# FORKGUARD_MAIN_BOARD.net
KiCad netlist of a schematic drawn in EasyEDA Pro
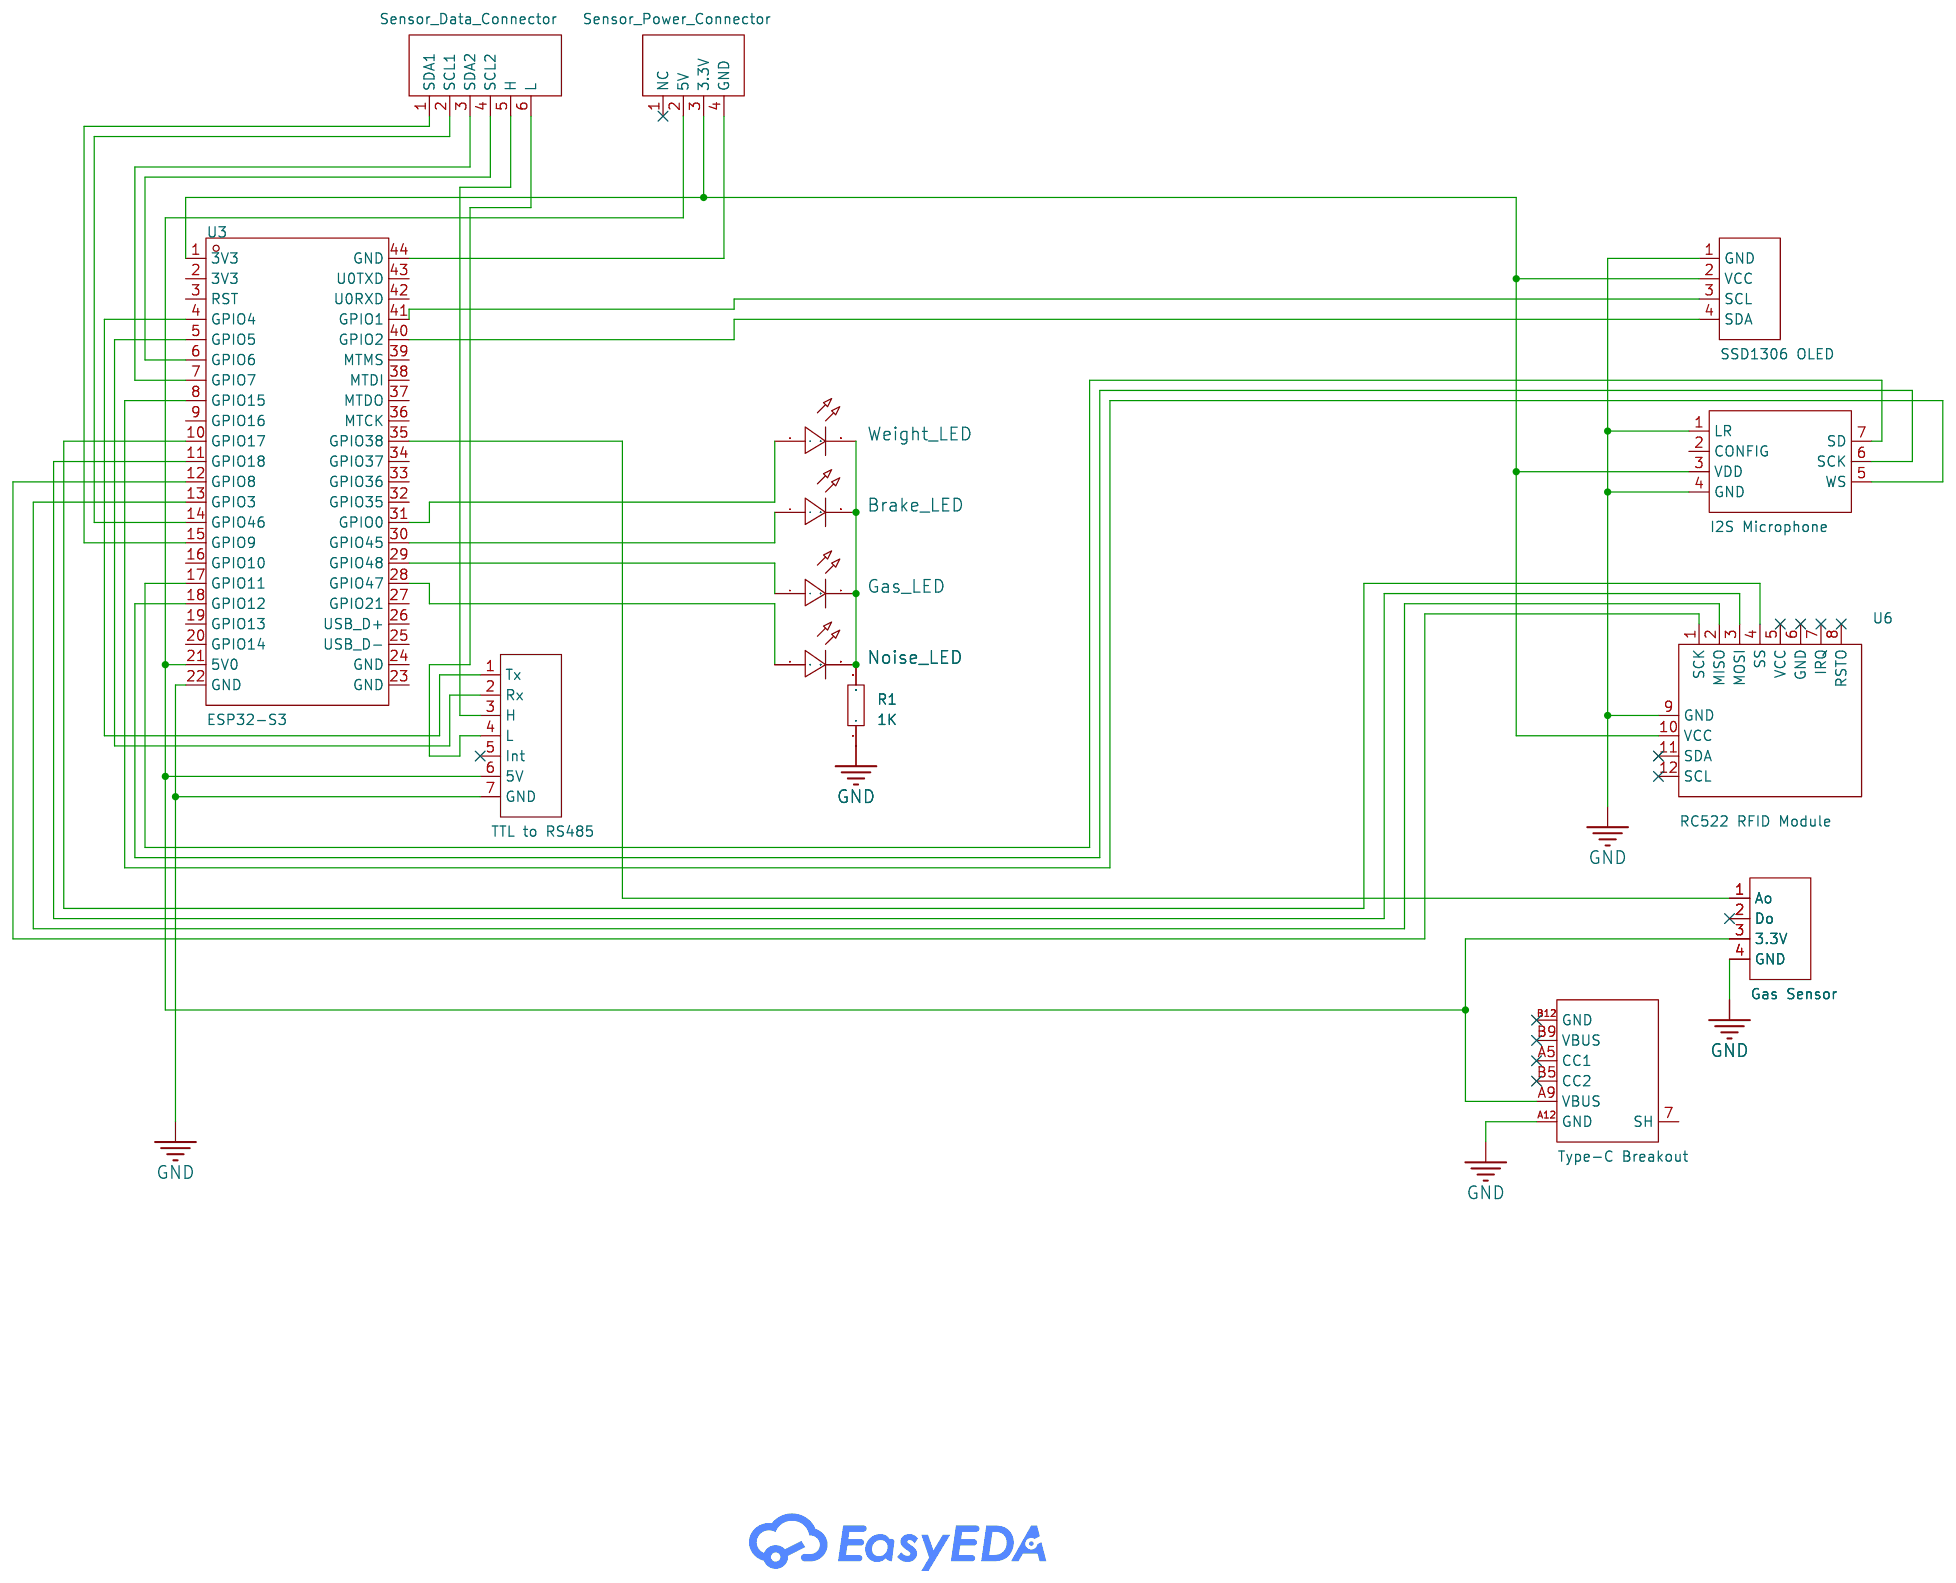
[diagram p0: schematic sheet]

(export (version "E")
  (design (tool "Eeschema 10.0.6"))
  (components
    (comp (ref "Brake_LED")
      (value "~")
      (footprint "easyedapro:LED0402-RD_YELLOW")
      (libsource (lib "easyedapro") (part "LED_R"))
    )
    (comp (ref "Display")
      (value "SSD1306 OLED")
      (footprint "easyedapro:OLED-TH_4P-L27.8-W27.3_MC096GW")
      (fields (field (name "Manufacturer Part") "MC096GW"))
      (libsource (lib "easyedapro") (part "MC096GW"))
    )
    (comp (ref "Gas_LED")
      (value "~")
      (footprint "easyedapro:LED0402-RD_YELLOW")
      (libsource (lib "easyedapro") (part "LED_R"))
    )
    (comp (ref "H1")
      (value "Sensor_Data_Connector")
      (footprint "easyedapro:HDR-TH_TW-06-01-T-S-150-085")
      (fields
        (field (name "Manufacturer Part") "TW-06-08-L-S-580-150")
        (field (name "Manufacturer") "SAMTEC")
      )
      (libsource (lib "easyedapro") (part "TW-06-08-L-S-580-150"))
    )
    (comp (ref "H2")
      (value "Sensor_Power_Connector")
      (footprint "easyedapro:HDR-TH_TW-04-06-T-S-433-120")
      (fields
        (field (name "Manufacturer Part") "TW-04-05-L-S-275-158")
        (field (name "Manufacturer") "SAMTEC")
      )
      (libsource (lib "easyedapro") (part "TW-04-05-L-S-275-158"))
    )
    (comp (ref "H5")
      (value "TTL to RS485")
      (footprint "easyedapro:HDR-TH_7P-P2.54_PBC07SAEN")
      (fields (field (name "Manufacturer Part") "PEC07SADN") (field (name "Manufacturer") "Sullins"))
      (libsource (lib "easyedapro") (part "PEC07SADN"))
    )
    (comp (ref "H6")
      (value "Gas Sensor")
      (footprint "easyedapro:HDR-TH_4P-P2.54-V-M_2")
      (fields (field (name "Manufacturer Part") "PEC04SFDN") (field (name "Manufacturer") "Sullins"))
      (libsource (lib "easyedapro") (part "PEC04SFDN"))
    )
    (comp (ref "Noise_LED")
      (value "~")
      (footprint "easyedapro:LED0402-RD_YELLOW")
      (libsource (lib "easyedapro") (part "LED_R"))
    )
    (comp (ref "R1") (value "10K") (footprint "easyedapro:R0603") (libsource (lib "easyedapro") (part "Res")))
    (comp (ref "U3")
      (value "ESP32-S3")
      (footprint "easyedapro:COMM-TH_L63.3-W25.4-P2.54-LS22.86")
      (fields (field (name "Manufacturer Part") "ESP32-S3-DEV-KIT-N8R8"))
      (libsource (lib "easyedapro") (part "ESP32-S3-DEV-KIT-N8R8"))
    )
    (comp (ref "U5")
      (value "I2S Microphone")
      (footprint "easyedapro:MIC-SMD_7P-L4.0-W3.0-P2.15-TL")
      (fields (field (name "Manufacturer Part") "DMM-4026-B-I2S-R") (field (name "Manufacturer") "PUIAUDIO"))
      (libsource (lib "easyedapro") (part "DMM-4026-B-I2S-R_C3171792"))
    )
    (comp (ref "U6")
      (value "RC522 RFID Module")
      (footprint "easyedapro:COMM-TH_L42.7-W40.4_PN532_NFC_RFID")
      (fields (field (name "Manufacturer Part") "PN532 NFC RFID Module v4"))
      (libsource (lib "easyedapro") (part "PN532 NFC RFID MODULE V4"))
    )
    (comp (ref "USB1")
      (value "Type-C Breakout")
      (footprint "easyedapro:USB-SMD_TYPE-C6P-ST")
      (fields (field (name "Manufacturer Part") "TCR51-65120601"))
      (libsource (lib "easyedapro") (part "TCR51-65120601"))
    )
    (comp (ref "Weight_LED")
      (value "~")
      (footprint "easyedapro:LED0402-RD_YELLOW")
      (libsource (lib "easyedapro") (part "LED_R"))
    )
  )
  (nets
    (net (code "1") (name "GND") (class "Default")
      (node (ref "Display") (pin "1") (pinfunction "GND_1") (pintype "unspecified"))
      (node (ref "H5") (pin "7") (pinfunction "GND_7") (pintype "unspecified"))
      (node (ref "H6") (pin "4") (pinfunction "GND_4") (pintype "unspecified"))
      (node (ref "R1") (pin "1") (pinfunction "1_1") (pintype "input"))
      (node (ref "U3") (pin "22") (pinfunction "GND_22") (pintype "unspecified"))
      (node (ref "U5") (pin "1") (pinfunction "LR_1") (pintype "unspecified"))
      (node (ref "U5") (pin "4") (pinfunction "GND_4") (pintype "unspecified"))
      (node (ref "U6") (pin "9") (pinfunction "GND_9") (pintype "unspecified"))
      (node (ref "USB1") (pin "A12") (pinfunction "GND_A12") (pintype "unspecified"))
    )
    (net (code "2") (name "Net-(Brake_LED-A)") (class "Default")
      (node (ref "Brake_LED") (pin "1") (pinfunction "A_1") (pintype "input"))
      (node (ref "U3") (pin "30") (pinfunction "GPIO45_30") (pintype "unspecified"))
    )
    (net (code "3") (name "Net-(Brake_LED-C)") (class "Default")
      (node (ref "Brake_LED") (pin "2") (pinfunction "C_2") (pintype "input"))
      (node (ref "Gas_LED") (pin "2") (pinfunction "C_2") (pintype "input"))
      (node (ref "Noise_LED") (pin "2") (pinfunction "C_2") (pintype "input"))
      (node (ref "R1") (pin "2") (pinfunction "2_2") (pintype "input"))
      (node (ref "Weight_LED") (pin "2") (pinfunction "C_2") (pintype "input"))
    )
    (net (code "4") (name "Net-(Display-SCL)") (class "Default")
      (node (ref "Display") (pin "3") (pinfunction "SCL_3") (pintype "unspecified"))
      (node (ref "U3") (pin "41") (pinfunction "GPIO1_41") (pintype "unspecified"))
    )
    (net (code "5") (name "Net-(Display-SDA)") (class "Default")
      (node (ref "Display") (pin "4") (pinfunction "SDA_4") (pintype "unspecified"))
      (node (ref "U3") (pin "40") (pinfunction "GPIO2_40") (pintype "unspecified"))
    )
    (net (code "6") (name "Net-(Display-VCC)") (class "Default")
      (node (ref "Display") (pin "2") (pinfunction "VCC_2") (pintype "unspecified"))
      (node (ref "H2") (pin "3") (pinfunction "3.3V_3") (pintype "unspecified"))
      (node (ref "U3") (pin "1") (pinfunction "3V3_1") (pintype "unspecified"))
      (node (ref "U5") (pin "3") (pinfunction "VDD_3") (pintype "unspecified"))
      (node (ref "U6") (pin "10") (pinfunction "VCC_10") (pintype "unspecified"))
    )
    (net (code "7") (name "Net-(Gas_LED-A)") (class "Default")
      (node (ref "Gas_LED") (pin "1") (pinfunction "A_1") (pintype "input"))
      (node (ref "U3") (pin "29") (pinfunction "GPIO48_29") (pintype "unspecified"))
    )
    (net (code "8") (name "Net-(H1-H)") (class "Default")
      (node (ref "H1") (pin "5") (pinfunction "H_5") (pintype "unspecified"))
      (node (ref "H5") (pin "3") (pinfunction "H_3") (pintype "unspecified"))
    )
    (net (code "9") (name "Net-(H1-L)") (class "Default")
      (node (ref "H1") (pin "6") (pinfunction "L_6") (pintype "unspecified"))
      (node (ref "H5") (pin "4") (pinfunction "L_4") (pintype "unspecified"))
    )
    (net (code "10") (name "Net-(H1-SCL1)") (class "Default")
      (node (ref "H1") (pin "2") (pinfunction "SCL1_2") (pintype "unspecified"))
      (node (ref "U3") (pin "14") (pinfunction "GPIO46_14") (pintype "unspecified"))
    )
    (net (code "11") (name "Net-(H1-SCL2)") (class "Default")
      (node (ref "H1") (pin "4") (pinfunction "SCL2_4") (pintype "unspecified"))
      (node (ref "U3") (pin "6") (pinfunction "GPIO6_6") (pintype "unspecified"))
    )
    (net (code "12") (name "Net-(H1-SDA1)") (class "Default")
      (node (ref "H1") (pin "1") (pinfunction "SDA1_1") (pintype "unspecified"))
      (node (ref "U3") (pin "15") (pinfunction "GPIO9_15") (pintype "unspecified"))
    )
    (net (code "13") (name "Net-(H1-SDA2)") (class "Default")
      (node (ref "H1") (pin "3") (pinfunction "SDA2_3") (pintype "unspecified"))
      (node (ref "U3") (pin "7") (pinfunction "GPIO7_7") (pintype "unspecified"))
    )
    (net (code "14") (name "Net-(H2-5V)") (class "Default")
      (node (ref "H2") (pin "2") (pinfunction "5V_2") (pintype "unspecified"))
      (node (ref "H5") (pin "6") (pinfunction "5V_6") (pintype "unspecified"))
      (node (ref "H6") (pin "3") (pinfunction "3.3V_3") (pintype "unspecified"))
      (node (ref "U3") (pin "21") (pinfunction "5V0_21") (pintype "unspecified"))
      (node (ref "USB1") (pin "A9") (pinfunction "VBUS_A9") (pintype "unspecified"))
    )
    (net (code "15") (name "Net-(H2-GND)") (class "Default")
      (node (ref "H2") (pin "4") (pinfunction "GND_4") (pintype "unspecified"))
      (node (ref "U3") (pin "44") (pinfunction "GND_44") (pintype "unspecified"))
    )
    (net (code "16") (name "Net-(H5-Rx)") (class "Default")
      (node (ref "H5") (pin "2") (pinfunction "Rx_2") (pintype "unspecified"))
      (node (ref "U3") (pin "5") (pinfunction "GPIO5_5") (pintype "unspecified"))
    )
    (net (code "17") (name "Net-(H5-Tx)") (class "Default")
      (node (ref "H5") (pin "1") (pinfunction "Tx_1") (pintype "unspecified"))
      (node (ref "U3") (pin "4") (pinfunction "GPIO4_4") (pintype "unspecified"))
    )
    (net (code "18") (name "Net-(H6-Ao)") (class "Default")
      (node (ref "H6") (pin "1") (pinfunction "Ao_1") (pintype "unspecified"))
      (node (ref "U3") (pin "35") (pinfunction "GPIO38_35") (pintype "unspecified"))
    )
    (net (code "19") (name "Net-(Noise_LED-A)") (class "Default")
      (node (ref "Noise_LED") (pin "1") (pinfunction "A_1") (pintype "input"))
      (node (ref "U3") (pin "28") (pinfunction "GPIO47_28") (pintype "unspecified"))
    )
    (net (code "20") (name "Net-(U3-GPIO0)") (class "Default")
      (node (ref "U3") (pin "31") (pinfunction "GPIO0_31") (pintype "unspecified"))
      (node (ref "Weight_LED") (pin "1") (pinfunction "A_1") (pintype "input"))
    )
    (net (code "21") (name "Net-(U3-GPIO3)") (class "Default")
      (node (ref "U3") (pin "13") (pinfunction "GPIO3_13") (pintype "unspecified"))
      (node (ref "U6") (pin "2") (pinfunction "MISO_2") (pintype "unspecified"))
    )
    (net (code "22") (name "Net-(U3-GPIO8)") (class "Default")
      (node (ref "U3") (pin "12") (pinfunction "GPIO8_12") (pintype "unspecified"))
      (node (ref "U6") (pin "1") (pinfunction "SCK_1") (pintype "unspecified"))
    )
    (net (code "23") (name "Net-(U3-GPIO11)") (class "Default")
      (node (ref "U3") (pin "17") (pinfunction "GPIO11_17") (pintype "unspecified"))
      (node (ref "U5") (pin "7") (pinfunction "SD_7") (pintype "unspecified"))
    )
    (net (code "24") (name "Net-(U3-GPIO12)") (class "Default")
      (node (ref "U3") (pin "18") (pinfunction "GPIO12_18") (pintype "unspecified"))
      (node (ref "U5") (pin "6") (pinfunction "SCK_6") (pintype "unspecified"))
    )
    (net (code "25") (name "Net-(U3-GPIO15)") (class "Default")
      (node (ref "U3") (pin "8") (pinfunction "GPIO15_8") (pintype "unspecified"))
      (node (ref "U5") (pin "5") (pinfunction "WS_5") (pintype "unspecified"))
    )
    (net (code "26") (name "Net-(U3-GPIO17)") (class "Default")
      (node (ref "U3") (pin "10") (pinfunction "GPIO17_10") (pintype "unspecified"))
      (node (ref "U6") (pin "4") (pinfunction "SS_4") (pintype "unspecified"))
    )
    (net (code "27") (name "Net-(U3-GPIO18)") (class "Default")
      (node (ref "U3") (pin "11") (pinfunction "GPIO18_11") (pintype "unspecified"))
      (node (ref "U6") (pin "3") (pinfunction "MOSI_3") (pintype "unspecified"))
    )
    (net (code "28") (name "unconnected-(H2-NC-Pad1)") (class "Default")
      (node (ref "H2") (pin "1") (pinfunction "NC_1") (pintype "unspecified+no_connect"))
    )
    (net (code "29") (name "unconnected-(H5-Int-Pad5)") (class "Default")
      (node (ref "H5") (pin "5") (pinfunction "Int_5") (pintype "unspecified+no_connect"))
    )
    (net (code "30") (name "unconnected-(H6-Do-Pad2)") (class "Default")
      (node (ref "H6") (pin "2") (pinfunction "Do_2") (pintype "unspecified+no_connect"))
    )
    (net (code "31") (name "unconnected-(U3-3V3-Pad2)") (class "Default")
      (node (ref "U3") (pin "2") (pinfunction "3V3_2") (pintype "unspecified"))
    )
    (net (code "32") (name "unconnected-(U3-GND-Pad23)") (class "Default")
      (node (ref "U3") (pin "23") (pinfunction "GND_23") (pintype "unspecified"))
    )
    (net (code "33") (name "unconnected-(U3-GND-Pad24)") (class "Default")
      (node (ref "U3") (pin "24") (pinfunction "GND_24") (pintype "unspecified"))
    )
    (net (code "34") (name "unconnected-(U3-GPIO10-Pad16)") (class "Default")
      (node (ref "U3") (pin "16") (pinfunction "GPIO10_16") (pintype "unspecified"))
    )
    (net (code "35") (name "unconnected-(U3-GPIO13-Pad19)") (class "Default")
      (node (ref "U3") (pin "19") (pinfunction "GPIO13_19") (pintype "unspecified"))
    )
    (net (code "36") (name "unconnected-(U3-GPIO14-Pad20)") (class "Default")
      (node (ref "U3") (pin "20") (pinfunction "GPIO14_20") (pintype "unspecified"))
    )
    (net (code "37") (name "unconnected-(U3-GPIO16-Pad9)") (class "Default")
      (node (ref "U3") (pin "9") (pinfunction "GPIO16_9") (pintype "unspecified"))
    )
    (net (code "38") (name "unconnected-(U3-GPIO21-Pad27)") (class "Default")
      (node (ref "U3") (pin "27") (pinfunction "GPIO21_27") (pintype "unspecified"))
    )
    (net (code "39") (name "unconnected-(U3-GPIO35-Pad32)") (class "Default")
      (node (ref "U3") (pin "32") (pinfunction "GPIO35_32") (pintype "unspecified"))
    )
    (net (code "40") (name "unconnected-(U3-GPIO36-Pad33)") (class "Default")
      (node (ref "U3") (pin "33") (pinfunction "GPIO36_33") (pintype "unspecified"))
    )
    (net (code "41") (name "unconnected-(U3-GPIO37-Pad34)") (class "Default")
      (node (ref "U3") (pin "34") (pinfunction "GPIO37_34") (pintype "unspecified"))
    )
    (net (code "42") (name "unconnected-(U3-MTCK-Pad36)") (class "Default")
      (node (ref "U3") (pin "36") (pinfunction "MTCK_36") (pintype "unspecified"))
    )
    (net (code "43") (name "unconnected-(U3-MTDI-Pad38)") (class "Default")
      (node (ref "U3") (pin "38") (pinfunction "MTDI_38") (pintype "unspecified"))
    )
    (net (code "44") (name "unconnected-(U3-MTDO-Pad37)") (class "Default")
      (node (ref "U3") (pin "37") (pinfunction "MTDO_37") (pintype "unspecified"))
    )
    (net (code "45") (name "unconnected-(U3-MTMS-Pad39)") (class "Default")
      (node (ref "U3") (pin "39") (pinfunction "MTMS_39") (pintype "unspecified"))
    )
    (net (code "46") (name "unconnected-(U3-RST-Pad3)") (class "Default")
      (node (ref "U3") (pin "3") (pinfunction "RST_3") (pintype "unspecified"))
    )
    (net (code "47") (name "unconnected-(U3-U0RXD-Pad42)") (class "Default")
      (node (ref "U3") (pin "42") (pinfunction "U0RXD_42") (pintype "unspecified"))
    )
    (net (code "48") (name "unconnected-(U3-U0TXD-Pad43)") (class "Default")
      (node (ref "U3") (pin "43") (pinfunction "U0TXD_43") (pintype "unspecified"))
    )
    (net (code "49") (name "unconnected-(U3-USB_D+-Pad26)") (class "Default")
      (node (ref "U3") (pin "26") (pinfunction "USB_D+_26") (pintype "unspecified"))
    )
    (net (code "50") (name "unconnected-(U3-USB_D--Pad25)") (class "Default")
      (node (ref "U3") (pin "25") (pinfunction "USB_D-_25") (pintype "unspecified"))
    )
    (net (code "51") (name "unconnected-(U5-CONFIG-Pad2)") (class "Default")
      (node (ref "U5") (pin "2") (pinfunction "CONFIG_2") (pintype "unspecified"))
    )
    (net (code "52") (name "unconnected-(U6-GND-Pad6)") (class "Default")
      (node (ref "U6") (pin "6") (pinfunction "GND_6") (pintype "unspecified+no_connect"))
    )
    (net (code "53") (name "unconnected-(U6-IRQ-Pad7)") (class "Default")
      (node (ref "U6") (pin "7") (pinfunction "IRQ_7") (pintype "unspecified+no_connect"))
    )
    (net (code "54") (name "unconnected-(U6-RSTO-Pad8)") (class "Default")
      (node (ref "U6") (pin "8") (pinfunction "RSTO_8") (pintype "unspecified+no_connect"))
    )
    (net (code "55") (name "unconnected-(U6-SCL-Pad12)") (class "Default")
      (node (ref "U6") (pin "12") (pinfunction "SCL_12") (pintype "unspecified+no_connect"))
    )
    (net (code "56") (name "unconnected-(U6-SDA-Pad11)") (class "Default")
      (node (ref "U6") (pin "11") (pinfunction "SDA_11") (pintype "unspecified+no_connect"))
    )
    (net (code "57") (name "unconnected-(U6-VCC-Pad5)") (class "Default")
      (node (ref "U6") (pin "5") (pinfunction "VCC_5") (pintype "unspecified+no_connect"))
    )
    (net (code "58") (name "unconnected-(USB1-CC1-PadA5)") (class "Default")
      (node (ref "USB1") (pin "A5") (pinfunction "CC1_A5") (pintype "unspecified+no_connect"))
    )
    (net (code "59") (name "unconnected-(USB1-CC2-PadB5)") (class "Default")
      (node (ref "USB1") (pin "B5") (pinfunction "CC2_B5") (pintype "unspecified+no_connect"))
    )
    (net (code "60") (name "unconnected-(USB1-GND-PadB12)") (class "Default")
      (node (ref "USB1") (pin "B12") (pinfunction "GND_B12") (pintype "unspecified+no_connect"))
    )
    (net (code "61") (name "unconnected-(USB1-SH-Pad7)") (class "Default")
      (node (ref "USB1") (pin "7") (pinfunction "SH_7") (pintype "unspecified"))
    )
    (net (code "62") (name "unconnected-(USB1-VBUS-PadB9)") (class "Default")
      (node (ref "USB1") (pin "B9") (pinfunction "VBUS_B9") (pintype "unspecified+no_connect"))
    )
  )
)
